# series_RLC.net
KiCad netlist of a schematic drawn in Altium Designer
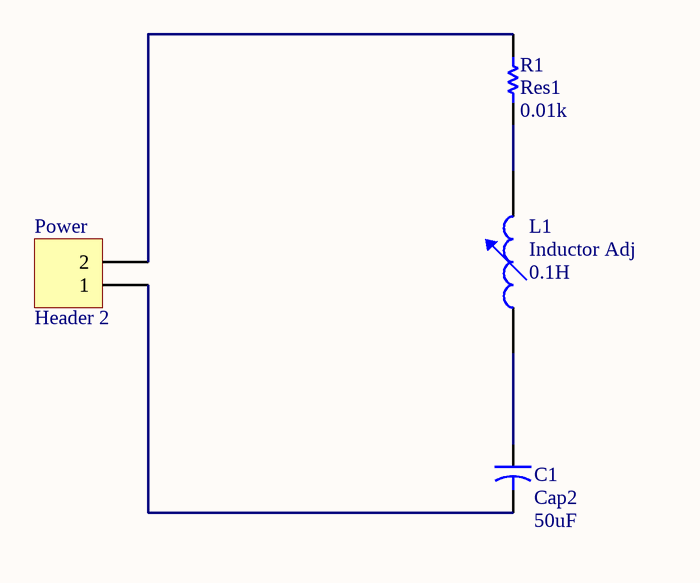
[diagram p0: series RLC.SchDoc]

(export (version "E")
  (design (tool "Eeschema 10.0.6"))
  (components
    (comp (ref "C1")
      (value "Cap2")
      (footprint "CAPR5-4X5")
      (description "Capacitor")
      (fields (field (name "ALTIUM_VALUE") "50uF") (field (name "PUBLISHER") "Altium Limited"))
      (libsource (lib "Miscellaneous Devices") (part "Cap2"))
    )
    (comp (ref "L1")
      (value "Inductor Adj")
      (footprint "AXIAL-0.8")
      (description "Adjustable Inductor")
      (fields (field (name "ALTIUM_VALUE") "0.1H") (field (name "PUBLISHER") "Altium Limited"))
      (libsource (lib "Miscellaneous Devices") (part "Inductor Adj"))
    )
    (comp (ref "Power")
      (value "Header 2")
      (footprint "HDR1X2")
      (description "Header, 2-Pin")
      (fields (field (name "PUBLISHER") "Altium Limited"))
      (libsource (lib "Miscellaneous Connectors") (part "Header 2"))
    )
    (comp (ref "R1")
      (value "Res1")
      (footprint "AXIAL-0.3")
      (description "Resistor")
      (fields (field (name "ALTIUM_VALUE") "0.01k") (field (name "PUBLISHER") "Altium Limited"))
      (libsource (lib "Miscellaneous Devices") (part "Res1"))
    )
  )
  (nets
    (net (code "1") (name "Net-(C1-Pad1)") (class "Default")
      (node (ref "C1") (pin "1") (pinfunction "1_1") (pintype "passive"))
      (node (ref "L1") (pin "1") (pinfunction "1_1") (pintype "passive"))
    )
    (net (code "2") (name "Net-(C1-Pad2)") (class "Default")
      (node (ref "C1") (pin "2") (pinfunction "2_2") (pintype "passive"))
      (node (ref "Power") (pin "1") (pinfunction "1_1") (pintype "passive"))
    )
    (net (code "3") (name "Net-(L1-Pad2)") (class "Default")
      (node (ref "L1") (pin "2") (pinfunction "2_2") (pintype "passive"))
      (node (ref "R1") (pin "1") (pinfunction "1_1") (pintype "passive"))
    )
    (net (code "4") (name "Net-(Power-Pad2)") (class "Default")
      (node (ref "Power") (pin "2") (pinfunction "2_2") (pintype "passive"))
      (node (ref "R1") (pin "2") (pinfunction "2_2") (pintype "passive"))
    )
  )
)
